# sparkfun-atsamd21g-breakout.net
KiCad netlist of a schematic drawn in EAGLE
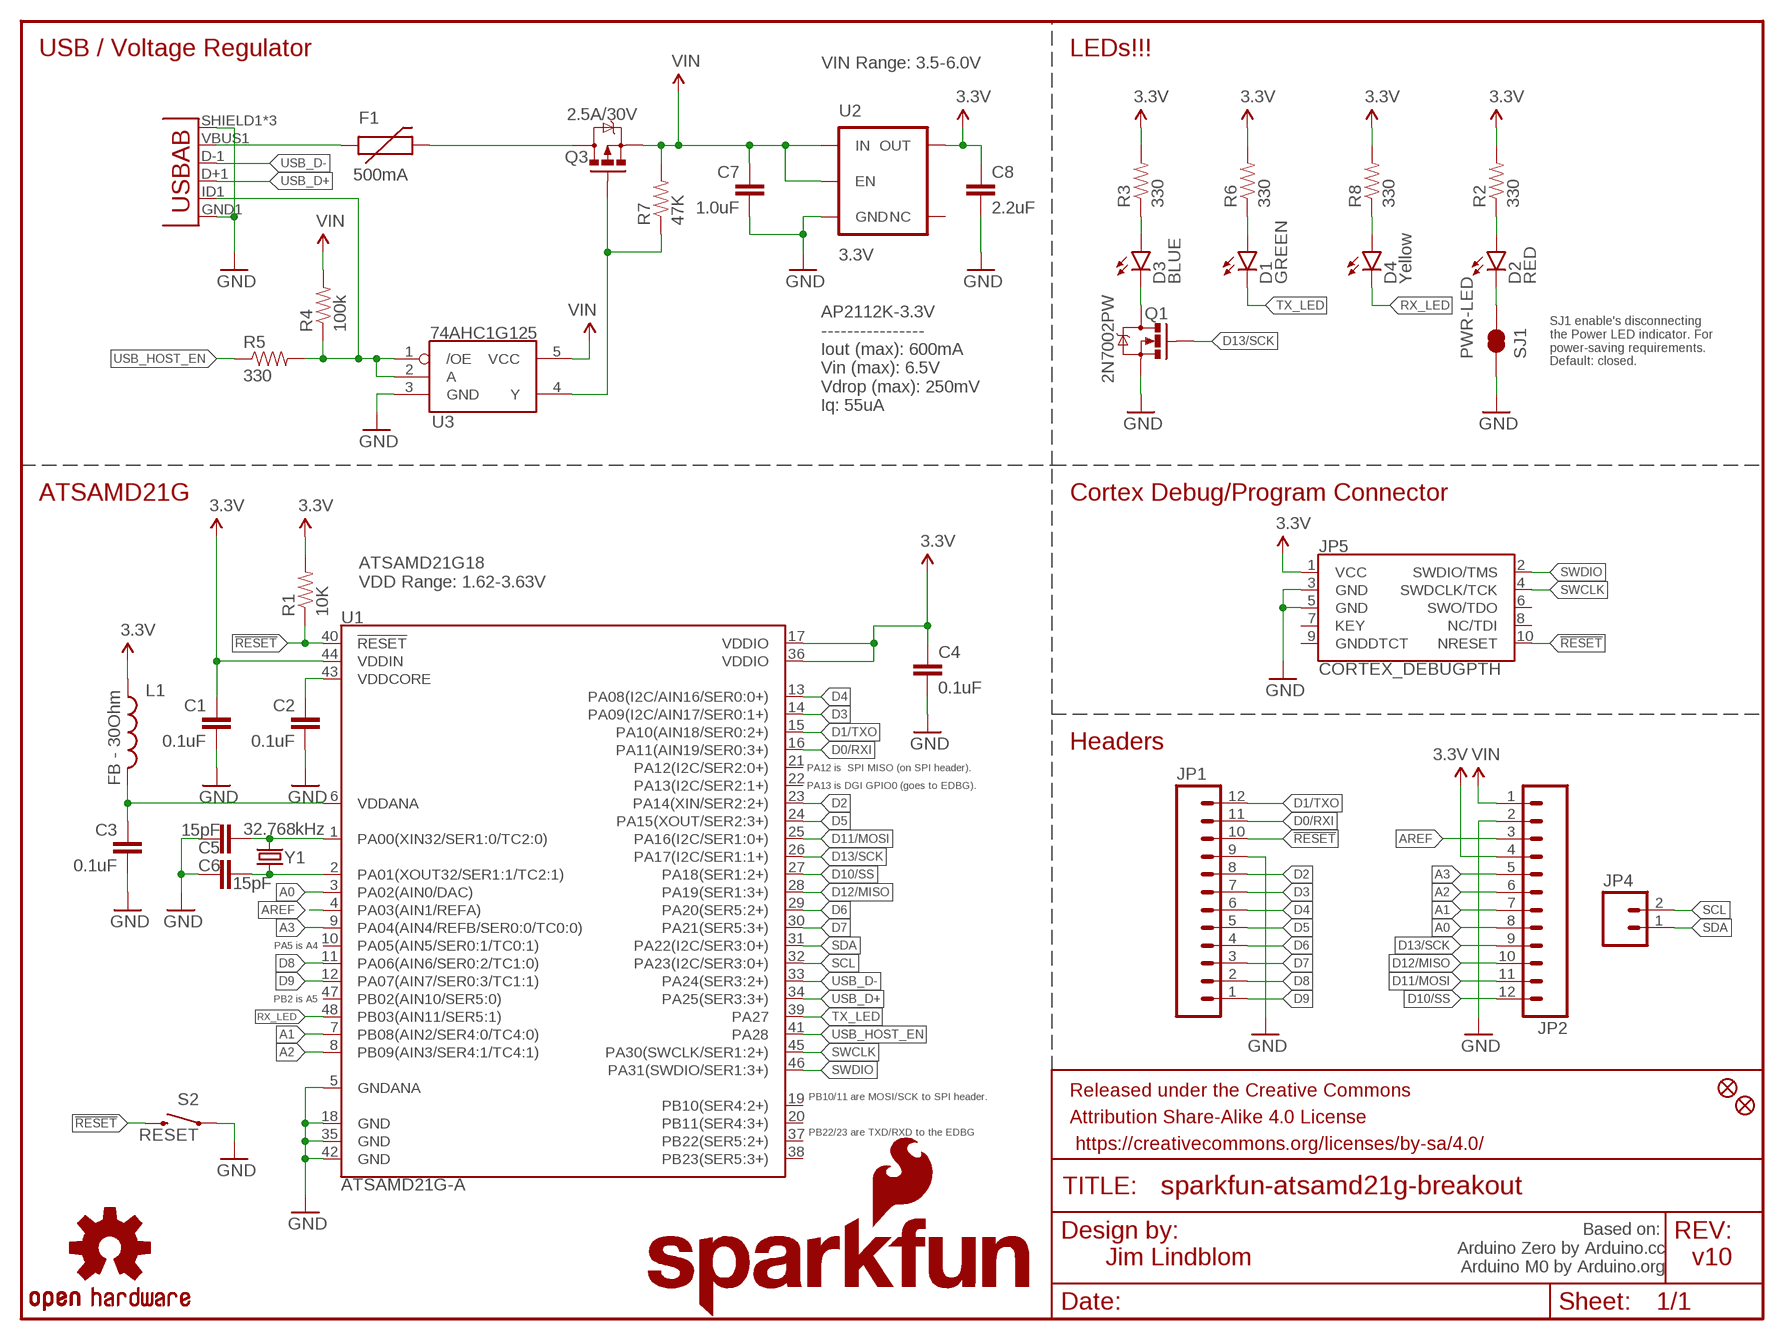
[diagram p0: schematic, sheet 1]

(export (version "E")
  (design (tool "Eeschema 10.0.6"))
  (components
    (comp (ref "C1")
      (value "0.1uF")
      (footprint "eagle-import:0402-CAP")
      (libsource (lib "eagle-import") (part "0.1UF-16V(+-10%)(0402)"))
    )
    (comp (ref "C2")
      (value "0.1uF")
      (footprint "eagle-import:0402-CAP")
      (libsource (lib "eagle-import") (part "0.1UF-16V(+-10%)(0402)"))
    )
    (comp (ref "C3")
      (value "0.1uF")
      (footprint "eagle-import:0402-CAP")
      (libsource (lib "eagle-import") (part "0.1UF-16V(+-10%)(0402)"))
    )
    (comp (ref "C4")
      (value "0.1uF")
      (footprint "eagle-import:0402-CAP")
      (libsource (lib "eagle-import") (part "0.1UF-16V(+-10%)(0402)"))
    )
    (comp (ref "C5")
      (value "15pF")
      (footprint "eagle-import:0402-CAP")
      (libsource (lib "eagle-import") (part "15PF-50V(+-5%)(0402)"))
    )
    (comp (ref "C6")
      (value "15pF")
      (footprint "eagle-import:0402-CAP")
      (libsource (lib "eagle-import") (part "15PF-50V(+-5%)(0402)"))
    )
    (comp (ref "C7")
      (value "1.0uF")
      (footprint "eagle-import:0805-CAP")
      (libsource (lib "eagle-import") (part "1.0UF-25V-+80/-20(0805){dblquote}"))
    )
    (comp (ref "C8")
      (value "2.2uF")
      (footprint "eagle-import:0603-CAP")
      (libsource (lib "eagle-import") (part "2.2UF-10V-20%(0603)"))
    )
    (comp (ref "D1")
      (value "GREEN")
      (footprint "eagle-import:LED-0603")
      (libsource (lib "eagle-import") (part "LED-GREEN0603"))
    )
    (comp (ref "D2")
      (value "RED")
      (footprint "eagle-import:LED-0603")
      (libsource (lib "eagle-import") (part "LED-RED0603"))
    )
    (comp (ref "D3")
      (value "BLUE")
      (footprint "eagle-import:LED-0603")
      (libsource (lib "eagle-import") (part "LED-BLUE0603"))
    )
    (comp (ref "D4")
      (value "Yellow")
      (footprint "eagle-import:LED-0603")
      (libsource (lib "eagle-import") (part "LED-YELLOW0603"))
    )
    (comp (ref "F1")
      (value "500mA")
      (footprint "eagle-import:PTC-1206")
      (libsource (lib "eagle-import") (part "PTCSMD"))
    )
    (comp (ref "FID1")
      (value "FIDUCIAL1X2")
      (footprint "eagle-import:FIDUCIAL-1X2")
      (libsource (lib "eagle-import") (part "FIDUCIAL1X2"))
    )
    (comp (ref "FID2")
      (value "FIDUCIAL1X2")
      (footprint "eagle-import:FIDUCIAL-1X2")
      (libsource (lib "eagle-import") (part "FIDUCIAL1X2"))
    )
    (comp (ref "FRAME1")
      (value "FRAME-LETTER")
      (footprint "eagle-import:CREATIVE_COMMONS")
      (libsource (lib "eagle-import") (part "FRAME-LETTER"))
    )
    (comp (ref "JP1")
      (value "M12NO_SILK")
      (footprint "eagle-import:1X12_NO_SILK")
      (libsource (lib "eagle-import") (part "M12NO_SILK"))
    )
    (comp (ref "JP2")
      (value "M12NO_SILK")
      (footprint "eagle-import:1X12_NO_SILK")
      (libsource (lib "eagle-import") (part "M12NO_SILK"))
    )
    (comp (ref "JP3")
      (value "USB-ABCONN-11794")
      (footprint "eagle-import:USB-AB-MICRO-SMD_V03")
      (libsource (lib "eagle-import") (part "USB-ABCONN-11794"))
    )
    (comp (ref "JP4")
      (value "M021X02_NO_SILK")
      (footprint "eagle-import:1X02_NO_SILK")
      (libsource (lib "eagle-import") (part "M021X02_NO_SILK"))
    )
    (comp (ref "JP5")
      (value "CORTEX_DEBUGPTH")
      (footprint "eagle-import:2X5-PTH-1.27MM")
      (libsource (lib "eagle-import") (part "CORTEX_DEBUGPTH"))
    )
    (comp (ref "L1")
      (value "FB - 30Ohm")
      (footprint "eagle-import:0603")
      (libsource (lib "eagle-import") (part "INDUCTOR0603"))
    )
    (comp (ref "LOGO1")
      (value "SFE_LOGO_FLAME.1_INCH")
      (footprint "eagle-import:SFE_LOGO_FLAME_.1")
      (libsource (lib "eagle-import") (part "SFE_LOGO_FLAME.1_INCH"))
    )
    (comp (ref "LOGO2")
      (value "OSHW-LOGOS")
      (footprint "eagle-import:OSHW-LOGO-S")
      (libsource (lib "eagle-import") (part "OSHW-LOGOS"))
    )
    (comp (ref "LOGO3")
      (value "SFE_LOGO_NAME_FLAME.1_INCH")
      (footprint "eagle-import:SFE_LOGO_NAME_FLAME_.1")
      (libsource (lib "eagle-import") (part "SFE_LOGO_NAME_FLAME.1_INCH"))
    )
    (comp (ref "Q1")
      (value "2N7002PW")
      (footprint "eagle-import:SOT323")
      (libsource (lib "eagle-import") (part "MOSFET-NCHANNEL2N7002PW"))
    )
    (comp (ref "Q3")
      (value "2.5A/30V")
      (footprint "eagle-import:SOT23-3")
      (libsource (lib "eagle-import") (part "MOSFET-PCHANNELDMG2307L"))
    )
    (comp (ref "R1")
      (value "10K")
      (footprint "eagle-import:0603-RES")
      (libsource (lib "eagle-import") (part "10KOHM-1/10W-1%(0603)0603"))
    )
    (comp (ref "R2")
      (value "330")
      (footprint "eagle-import:0603-RES")
      (libsource (lib "eagle-import") (part "330OHM1/10W1%(0603)"))
    )
    (comp (ref "R3")
      (value "330")
      (footprint "eagle-import:0603-RES")
      (libsource (lib "eagle-import") (part "330OHM1/10W1%(0603)"))
    )
    (comp (ref "R4")
      (value "100k")
      (footprint "eagle-import:0603-RES")
      (libsource (lib "eagle-import") (part "100KOHM-1/10W-1%(0603)"))
    )
    (comp (ref "R5")
      (value "330")
      (footprint "eagle-import:0603-RES")
      (libsource (lib "eagle-import") (part "330OHM1/10W1%(0603)"))
    )
    (comp (ref "R6")
      (value "330")
      (footprint "eagle-import:0603-RES")
      (libsource (lib "eagle-import") (part "330OHM1/10W1%(0603)"))
    )
    (comp (ref "R7")
      (value "47K")
      (footprint "eagle-import:0603-RES")
      (libsource (lib "eagle-import") (part "47KOHM1/10W1%(0603)"))
    )
    (comp (ref "R8")
      (value "330")
      (footprint "eagle-import:0603-RES")
      (libsource (lib "eagle-import") (part "330OHM1/10W1%(0603)"))
    )
    (comp (ref "S2")
      (value "RESET")
      (footprint "eagle-import:TACTILE_SWITCH_SMD_4.6X2.8MM")
      (libsource (lib "eagle-import") (part "SWITCH-MOMENTARY-2SMD-4.6X2.8MM"))
    )
    (comp (ref "SJ1")
      (value "PWR-LED")
      (footprint "eagle-import:PAD-JUMPER-2-NC_BY_TRACE_NO_SILK")
      (libsource (lib "eagle-import") (part "JUMPER-PAD-2-NC_BY_TRACENO_SILK"))
    )
    (comp (ref "U1")
      (value "ATSAMD21G-A")
      (footprint "eagle-import:TQFP-48")
      (libsource (lib "eagle-import") (part "ATSAMD21G-A"))
    )
    (comp (ref "U2")
      (value "3.3V")
      (footprint "eagle-import:SOT23-5")
      (libsource (lib "eagle-import") (part "V_REG_AP2112K-3.3V"))
    )
    (comp (ref "U3")
      (value "74AHC1G125")
      (footprint "eagle-import:SOT23-5")
      (libsource (lib "eagle-import") (part "74AHC1G125"))
    )
    (comp (ref "Y1")
      (value "32.768kHz")
      (footprint "eagle-import:CRYSTAL-SMD-3.2X1.5MM")
      (libsource (lib "eagle-import") (part "CRYSTAL3.2X1.5MM"))
    )
  )
  (nets
    (net (code "1") (name "/~{RESET}") (class "Default")
      (node (ref "JP1") (pin "10") (pinfunction "10_10") (pintype "passive"))
      (node (ref "JP5") (pin "10") (pinfunction "NRESET_10") (pintype "bidirectional"))
      (node (ref "R1") (pin "1") (pinfunction "1_1") (pintype "passive"))
      (node (ref "S2") (pin "3") (pinfunction "2_3") (pintype "passive"))
      (node (ref "S2") (pin "4") (pinfunction "2_4") (pintype "passive"))
      (node (ref "U1") (pin "40") (pinfunction "~{RESET}_40") (pintype "bidirectional"))
    )
    (net (code "2") (name "3.3V") (class "Default")
      (node (ref "C1") (pin "1") (pinfunction "1_1") (pintype "passive"))
      (node (ref "C4") (pin "1") (pinfunction "1_1") (pintype "passive"))
      (node (ref "C8") (pin "1") (pinfunction "1_1") (pintype "passive"))
      (node (ref "JP2") (pin "4") (pinfunction "4_4") (pintype "passive"))
      (node (ref "JP5") (pin "1") (pinfunction "VCC_1") (pintype "bidirectional"))
      (node (ref "L1") (pin "1") (pinfunction "1_1") (pintype "passive"))
      (node (ref "R1") (pin "2") (pinfunction "2_2") (pintype "passive"))
      (node (ref "R2") (pin "2") (pinfunction "2_2") (pintype "passive"))
      (node (ref "R3") (pin "2") (pinfunction "2_2") (pintype "passive"))
      (node (ref "R6") (pin "2") (pinfunction "2_2") (pintype "passive"))
      (node (ref "R8") (pin "2") (pinfunction "2_2") (pintype "passive"))
      (node (ref "U1") (pin "17") (pinfunction "VDDIO_17") (pintype "bidirectional"))
      (node (ref "U1") (pin "36") (pinfunction "VDDIO_36") (pintype "bidirectional"))
      (node (ref "U1") (pin "44") (pinfunction "VDDIN_44") (pintype "bidirectional"))
      (node (ref "U2") (pin "5") (pinfunction "OUT_5") (pintype "passive"))
    )
    (net (code "3") (name "A0") (class "Default")
      (node (ref "JP2") (pin "8") (pinfunction "8_8") (pintype "passive"))
      (node (ref "U1") (pin "3") (pinfunction "PA02(AIN0/DAC)_3") (pintype "bidirectional"))
    )
    (net (code "4") (name "A1") (class "Default")
      (node (ref "JP2") (pin "7") (pinfunction "7_7") (pintype "passive"))
      (node (ref "U1") (pin "7") (pinfunction "PB08(AIN2/SER4:0/TC4:0)_7") (pintype "bidirectional"))
    )
    (net (code "5") (name "A2") (class "Default")
      (node (ref "JP2") (pin "6") (pinfunction "6_6") (pintype "passive"))
      (node (ref "U1") (pin "8") (pinfunction "PB09(AIN3/SER4:1/TC4:1)_8") (pintype "bidirectional"))
    )
    (net (code "6") (name "A3") (class "Default")
      (node (ref "JP2") (pin "5") (pinfunction "5_5") (pintype "passive"))
      (node (ref "U1") (pin "9") (pinfunction "PA04(AIN4/REFB/SER0:0/TC0:0)_9") (pintype "bidirectional"))
    )
    (net (code "7") (name "AREF") (class "Default")
      (node (ref "JP2") (pin "3") (pinfunction "3_3") (pintype "passive"))
      (node (ref "U1") (pin "4") (pinfunction "PA03(AIN1/REFA)_4") (pintype "bidirectional"))
    )
    (net (code "8") (name "D0{slash}RXI") (class "Default")
      (node (ref "JP1") (pin "11") (pinfunction "11_11") (pintype "passive"))
      (node (ref "U1") (pin "16") (pinfunction "PA11(AIN19/SER0:3+)_16") (pintype "bidirectional"))
    )
    (net (code "9") (name "D1{slash}TXO") (class "Default")
      (node (ref "JP1") (pin "12") (pinfunction "12_12") (pintype "passive"))
      (node (ref "U1") (pin "15") (pinfunction "PA10(AIN18/SER0:2+)_15") (pintype "bidirectional"))
    )
    (net (code "10") (name "D2") (class "Default")
      (node (ref "JP1") (pin "8") (pinfunction "8_8") (pintype "passive"))
      (node (ref "U1") (pin "23") (pinfunction "PA14(XIN/SER2:2+)_23") (pintype "bidirectional"))
    )
    (net (code "11") (name "D3") (class "Default")
      (node (ref "JP1") (pin "7") (pinfunction "7_7") (pintype "passive"))
      (node (ref "U1") (pin "14") (pinfunction "PA09(I2C/AIN17/SER0:1+)_14") (pintype "bidirectional"))
    )
    (net (code "12") (name "D4") (class "Default")
      (node (ref "JP1") (pin "6") (pinfunction "6_6") (pintype "passive"))
      (node (ref "U1") (pin "13") (pinfunction "PA08(I2C/AIN16/SER0:0+)_13") (pintype "bidirectional"))
    )
    (net (code "13") (name "D5") (class "Default")
      (node (ref "JP1") (pin "5") (pinfunction "5_5") (pintype "passive"))
      (node (ref "U1") (pin "24") (pinfunction "PA15(XOUT/SER2:3+)_24") (pintype "bidirectional"))
    )
    (net (code "14") (name "D6") (class "Default")
      (node (ref "JP1") (pin "4") (pinfunction "4_4") (pintype "passive"))
      (node (ref "U1") (pin "29") (pinfunction "PA20(SER5:2+)_29") (pintype "bidirectional"))
    )
    (net (code "15") (name "D7") (class "Default")
      (node (ref "JP1") (pin "3") (pinfunction "3_3") (pintype "passive"))
      (node (ref "U1") (pin "30") (pinfunction "PA21(SER5:3+)_30") (pintype "bidirectional"))
    )
    (net (code "16") (name "D8") (class "Default")
      (node (ref "JP1") (pin "2") (pinfunction "2_2") (pintype "passive"))
      (node (ref "U1") (pin "11") (pinfunction "PA06(AIN6/SER0:2/TC1:0)_11") (pintype "bidirectional"))
    )
    (net (code "17") (name "D9") (class "Default")
      (node (ref "JP1") (pin "1") (pinfunction "1_1") (pintype "passive"))
      (node (ref "U1") (pin "12") (pinfunction "PA07(AIN7/SER0:3/TC1:1)_12") (pintype "bidirectional"))
    )
    (net (code "18") (name "D10{slash}SS") (class "Default")
      (node (ref "JP2") (pin "12") (pinfunction "12_12") (pintype "passive"))
      (node (ref "U1") (pin "27") (pinfunction "PA18(SER1:2+)_27") (pintype "bidirectional"))
    )
    (net (code "19") (name "D11{slash}MOSI") (class "Default")
      (node (ref "JP2") (pin "11") (pinfunction "11_11") (pintype "passive"))
      (node (ref "U1") (pin "25") (pinfunction "PA16(I2C/SER1:0+)_25") (pintype "bidirectional"))
    )
    (net (code "20") (name "D12{slash}MISO") (class "Default")
      (node (ref "JP2") (pin "10") (pinfunction "10_10") (pintype "passive"))
      (node (ref "U1") (pin "28") (pinfunction "PA19(SER1:3+)_28") (pintype "bidirectional"))
    )
    (net (code "21") (name "D13{slash}SCK") (class "Default")
      (node (ref "JP2") (pin "9") (pinfunction "9_9") (pintype "passive"))
      (node (ref "Q1") (pin "1") (pinfunction "G_1") (pintype "passive"))
      (node (ref "U1") (pin "26") (pinfunction "PA17(I2C/SER1:1+)_26") (pintype "bidirectional"))
    )
    (net (code "22") (name "GND") (class "Default")
      (node (ref "C1") (pin "2") (pinfunction "2_2") (pintype "passive"))
      (node (ref "C2") (pin "2") (pinfunction "2_2") (pintype "passive"))
      (node (ref "C3") (pin "2") (pinfunction "2_2") (pintype "passive"))
      (node (ref "C4") (pin "2") (pinfunction "2_2") (pintype "passive"))
      (node (ref "C5") (pin "1") (pinfunction "1_1") (pintype "passive"))
      (node (ref "C6") (pin "2") (pinfunction "2_2") (pintype "passive"))
      (node (ref "C7") (pin "2") (pinfunction "2_2") (pintype "passive"))
      (node (ref "C8") (pin "2") (pinfunction "2_2") (pintype "passive"))
      (node (ref "JP1") (pin "9") (pinfunction "9_9") (pintype "passive"))
      (node (ref "JP2") (pin "2") (pinfunction "2_2") (pintype "passive"))
      (node (ref "JP3") (pin "GND1") (pinfunction "GND_GND1") (pintype "bidirectional"))
      (node (ref "JP3") (pin "SHIELD1") (pinfunction "SHIELD_SHIELD1") (pintype "bidirectional"))
      (node (ref "JP3") (pin "SHIELD2") (pinfunction "SHIELD_SHIELD2") (pintype "bidirectional"))
      (node (ref "JP3") (pin "SHIELD3") (pinfunction "SHIELD_SHIELD3") (pintype "bidirectional"))
      (node (ref "JP5") (pin "3") (pinfunction "GND_3") (pintype "bidirectional"))
      (node (ref "JP5") (pin "5") (pinfunction "GND_5") (pintype "bidirectional"))
      (node (ref "Q1") (pin "2") (pinfunction "S_2") (pintype "passive"))
      (node (ref "S2") (pin "1") (pinfunction "1_1") (pintype "passive"))
      (node (ref "S2") (pin "2") (pinfunction "1_2") (pintype "passive"))
      (node (ref "SJ1") (pin "1") (pinfunction "1_1") (pintype "passive"))
      (node (ref "U1") (pin "18") (pinfunction "GND_18") (pintype "bidirectional"))
      (node (ref "U1") (pin "35") (pinfunction "GND_35") (pintype "bidirectional"))
      (node (ref "U1") (pin "42") (pinfunction "GND_42") (pintype "bidirectional"))
      (node (ref "U1") (pin "5") (pinfunction "GNDANA_5") (pintype "bidirectional"))
      (node (ref "U2") (pin "2") (pinfunction "GND_2") (pintype "input"))
      (node (ref "U3") (pin "3") (pinfunction "GND_3") (pintype "bidirectional"))
    )
    (net (code "23") (name "Net-(D1-PadA)") (class "Default")
      (node (ref "D1") (pin "A") (pinfunction "A_A") (pintype "passive"))
      (node (ref "R6") (pin "1") (pinfunction "1_1") (pintype "passive"))
    )
    (net (code "24") (name "Net-(D2-PadA)") (class "Default")
      (node (ref "D2") (pin "A") (pinfunction "A_A") (pintype "passive"))
      (node (ref "R2") (pin "1") (pinfunction "1_1") (pintype "passive"))
    )
    (net (code "25") (name "Net-(D2-PadC)") (class "Default")
      (node (ref "D2") (pin "C") (pinfunction "C_C") (pintype "passive"))
      (node (ref "SJ1") (pin "2") (pinfunction "2_2") (pintype "passive"))
    )
    (net (code "26") (name "Net-(D3-PadA)") (class "Default")
      (node (ref "D3") (pin "A") (pinfunction "A_A") (pintype "passive"))
      (node (ref "R3") (pin "1") (pinfunction "1_1") (pintype "passive"))
    )
    (net (code "27") (name "Net-(D4-PadA)") (class "Default")
      (node (ref "D4") (pin "A") (pinfunction "A_A") (pintype "passive"))
      (node (ref "R8") (pin "1") (pinfunction "1_1") (pintype "passive"))
    )
    (net (code "28") (name "Net-(JP3-USBID)") (class "Default")
      (node (ref "JP3") (pin "ID1") (pinfunction "USBID_ID1") (pintype "bidirectional"))
      (node (ref "R4") (pin "1") (pinfunction "1_1") (pintype "passive"))
      (node (ref "R5") (pin "2") (pinfunction "2_2") (pintype "passive"))
      (node (ref "U3") (pin "1") (pinfunction "/OE_1") (pintype "bidirectional"))
      (node (ref "U3") (pin "2") (pinfunction "A_2") (pintype "bidirectional"))
    )
    (net (code "29") (name "Net-(JP3-VBUS)") (class "Default")
      (node (ref "F1") (pin "1") (pinfunction "1_1") (pintype "bidirectional"))
      (node (ref "JP3") (pin "VBUS1") (pinfunction "VBUS_VBUS1") (pintype "bidirectional"))
    )
    (net (code "30") (name "Net-(Q1-D)") (class "Default")
      (node (ref "D3") (pin "C") (pinfunction "C_C") (pintype "passive"))
      (node (ref "Q1") (pin "3") (pinfunction "D_3") (pintype "passive"))
    )
    (net (code "31") (name "Net-(Q3-D)") (class "Default")
      (node (ref "F1") (pin "2") (pinfunction "2_2") (pintype "bidirectional"))
      (node (ref "Q3") (pin "3") (pinfunction "D_3") (pintype "passive"))
    )
    (net (code "32") (name "Net-(Q3-G)") (class "Default")
      (node (ref "Q3") (pin "1") (pinfunction "G_1") (pintype "passive"))
      (node (ref "R7") (pin "1") (pinfunction "1_1") (pintype "passive"))
      (node (ref "U3") (pin "4") (pinfunction "Y_4") (pintype "bidirectional"))
    )
    (net (code "33") (name "Net-(U1-PA00(XIN32{slash}SER1:0{slash}TC2:0))") (class "Default")
      (node (ref "C5") (pin "2") (pinfunction "2_2") (pintype "passive"))
      (node (ref "U1") (pin "1") (pinfunction "PA00(XIN32/SER1:0/TC2:0)_1") (pintype "bidirectional"))
      (node (ref "Y1") (pin "P$2") (pinfunction "2_P$2") (pintype "passive"))
    )
    (net (code "34") (name "Net-(U1-PA01(XOUT32{slash}SER1:1{slash}TC2:1))") (class "Default")
      (node (ref "C6") (pin "1") (pinfunction "1_1") (pintype "passive"))
      (node (ref "U1") (pin "2") (pinfunction "PA01(XOUT32/SER1:1/TC2:1)_2") (pintype "bidirectional"))
      (node (ref "Y1") (pin "P$1") (pinfunction "1_P$1") (pintype "passive"))
    )
    (net (code "35") (name "Net-(U1-VDDANA)") (class "Default")
      (node (ref "C3") (pin "1") (pinfunction "1_1") (pintype "passive"))
      (node (ref "L1") (pin "2") (pinfunction "2_2") (pintype "passive"))
      (node (ref "U1") (pin "6") (pinfunction "VDDANA_6") (pintype "bidirectional"))
    )
    (net (code "36") (name "Net-(U1-VDDCORE)") (class "Default")
      (node (ref "C2") (pin "1") (pinfunction "1_1") (pintype "passive"))
      (node (ref "U1") (pin "43") (pinfunction "VDDCORE_43") (pintype "bidirectional"))
    )
    (net (code "37") (name "RX_LED") (class "Default")
      (node (ref "D4") (pin "C") (pinfunction "C_C") (pintype "passive"))
      (node (ref "U1") (pin "48") (pinfunction "PB03(AIN11/SER5:1)_48") (pintype "bidirectional"))
    )
    (net (code "38") (name "SCL") (class "Default")
      (node (ref "JP4") (pin "2") (pinfunction "2_2") (pintype "passive"))
      (node (ref "U1") (pin "32") (pinfunction "PA23(I2C/SER3:0+)_32") (pintype "bidirectional"))
    )
    (net (code "39") (name "SDA") (class "Default")
      (node (ref "JP4") (pin "1") (pinfunction "1_1") (pintype "passive"))
      (node (ref "U1") (pin "31") (pinfunction "PA22(I2C/SER3:0+)_31") (pintype "bidirectional"))
    )
    (net (code "40") (name "SWCLK") (class "Default")
      (node (ref "JP5") (pin "4") (pinfunction "SWDCLK/TCK_4") (pintype "bidirectional"))
      (node (ref "U1") (pin "45") (pinfunction "PA30(SWCLK/SER1:2+)_45") (pintype "bidirectional"))
    )
    (net (code "41") (name "SWDIO") (class "Default")
      (node (ref "JP5") (pin "2") (pinfunction "SWDIO/TMS_2") (pintype "bidirectional"))
      (node (ref "U1") (pin "46") (pinfunction "PA31(SWDIO/SER1:3+)_46") (pintype "bidirectional"))
    )
    (net (code "42") (name "TX_LED") (class "Default")
      (node (ref "D1") (pin "C") (pinfunction "C_C") (pintype "passive"))
      (node (ref "U1") (pin "39") (pinfunction "PA27_39") (pintype "bidirectional"))
    )
    (net (code "43") (name "USB_D+") (class "Default")
      (node (ref "JP3") (pin "D+1") (pinfunction "D+_D+1") (pintype "bidirectional"))
      (node (ref "U1") (pin "34") (pinfunction "PA25(SER3:3+)_34") (pintype "bidirectional"))
    )
    (net (code "44") (name "USB_D-") (class "Default")
      (node (ref "JP3") (pin "D-1") (pinfunction "D-_D-1") (pintype "bidirectional"))
      (node (ref "U1") (pin "33") (pinfunction "PA24(SER3:2+)_33") (pintype "bidirectional"))
    )
    (net (code "45") (name "USB_HOST_EN") (class "Default")
      (node (ref "R5") (pin "1") (pinfunction "1_1") (pintype "passive"))
      (node (ref "U1") (pin "41") (pinfunction "PA28_41") (pintype "bidirectional"))
    )
    (net (code "46") (name "VIN") (class "Default")
      (node (ref "C7") (pin "1") (pinfunction "1_1") (pintype "passive"))
      (node (ref "JP2") (pin "1") (pinfunction "1_1") (pintype "passive"))
      (node (ref "Q3") (pin "2") (pinfunction "S_2") (pintype "passive"))
      (node (ref "R4") (pin "2") (pinfunction "2_2") (pintype "passive"))
      (node (ref "R7") (pin "2") (pinfunction "2_2") (pintype "passive"))
      (node (ref "U2") (pin "1") (pinfunction "IN_1") (pintype "input"))
      (node (ref "U2") (pin "3") (pinfunction "EN_3") (pintype "input"))
      (node (ref "U3") (pin "5") (pinfunction "VCC_5") (pintype "bidirectional"))
    )
    (net (code "47") (name "unconnected-(JP5-GNDDTCT-Pad9)") (class "Default")
      (node (ref "JP5") (pin "9") (pinfunction "GNDDTCT_9") (pintype "bidirectional"))
    )
    (net (code "48") (name "unconnected-(JP5-KEY-Pad7)") (class "Default")
      (node (ref "JP5") (pin "7") (pinfunction "KEY_7") (pintype "bidirectional"))
    )
    (net (code "49") (name "unconnected-(JP5-NC{slash}TDI-Pad8)") (class "Default")
      (node (ref "JP5") (pin "8") (pinfunction "NC/TDI_8") (pintype "bidirectional"))
    )
    (net (code "50") (name "unconnected-(JP5-SWO{slash}TDO-Pad6)") (class "Default")
      (node (ref "JP5") (pin "6") (pinfunction "SWO/TDO_6") (pintype "bidirectional"))
    )
    (net (code "51") (name "unconnected-(U1-PA05(AIN5{slash}SER0:1{slash}TC0:1)-Pad10)") (class "Default")
      (node (ref "U1") (pin "10") (pinfunction "PA05(AIN5/SER0:1/TC0:1)_10") (pintype "bidirectional"))
    )
    (net (code "52") (name "unconnected-(U1-PA12(I2C{slash}SER2:0+)-Pad21)") (class "Default")
      (node (ref "U1") (pin "21") (pinfunction "PA12(I2C/SER2:0+)_21") (pintype "bidirectional"))
    )
    (net (code "53") (name "unconnected-(U1-PA13(I2C{slash}SER2:1+)-Pad22)") (class "Default")
      (node (ref "U1") (pin "22") (pinfunction "PA13(I2C/SER2:1+)_22") (pintype "bidirectional"))
    )
    (net (code "54") (name "unconnected-(U1-PB02(AIN10{slash}SER5:0)-Pad47)") (class "Default")
      (node (ref "U1") (pin "47") (pinfunction "PB02(AIN10/SER5:0)_47") (pintype "bidirectional"))
    )
    (net (code "55") (name "unconnected-(U1-PB10(SER4:2+)-Pad19)") (class "Default")
      (node (ref "U1") (pin "19") (pinfunction "PB10(SER4:2+)_19") (pintype "bidirectional"))
    )
    (net (code "56") (name "unconnected-(U1-PB11(SER4:3+)-Pad20)") (class "Default")
      (node (ref "U1") (pin "20") (pinfunction "PB11(SER4:3+)_20") (pintype "bidirectional"))
    )
    (net (code "57") (name "unconnected-(U1-PB22(SER5:2+)-Pad37)") (class "Default")
      (node (ref "U1") (pin "37") (pinfunction "PB22(SER5:2+)_37") (pintype "bidirectional"))
    )
    (net (code "58") (name "unconnected-(U1-PB23(SER5:3+)-Pad38)") (class "Default")
      (node (ref "U1") (pin "38") (pinfunction "PB23(SER5:3+)_38") (pintype "bidirectional"))
    )
    (net (code "59") (name "unconnected-(U2-NC-Pad4)") (class "Default")
      (node (ref "U2") (pin "4") (pinfunction "NC_4") (pintype "input"))
    )
  )
)
